# SPTSquidBoard.net
KiCad netlist of a schematic drawn in Altium Designer
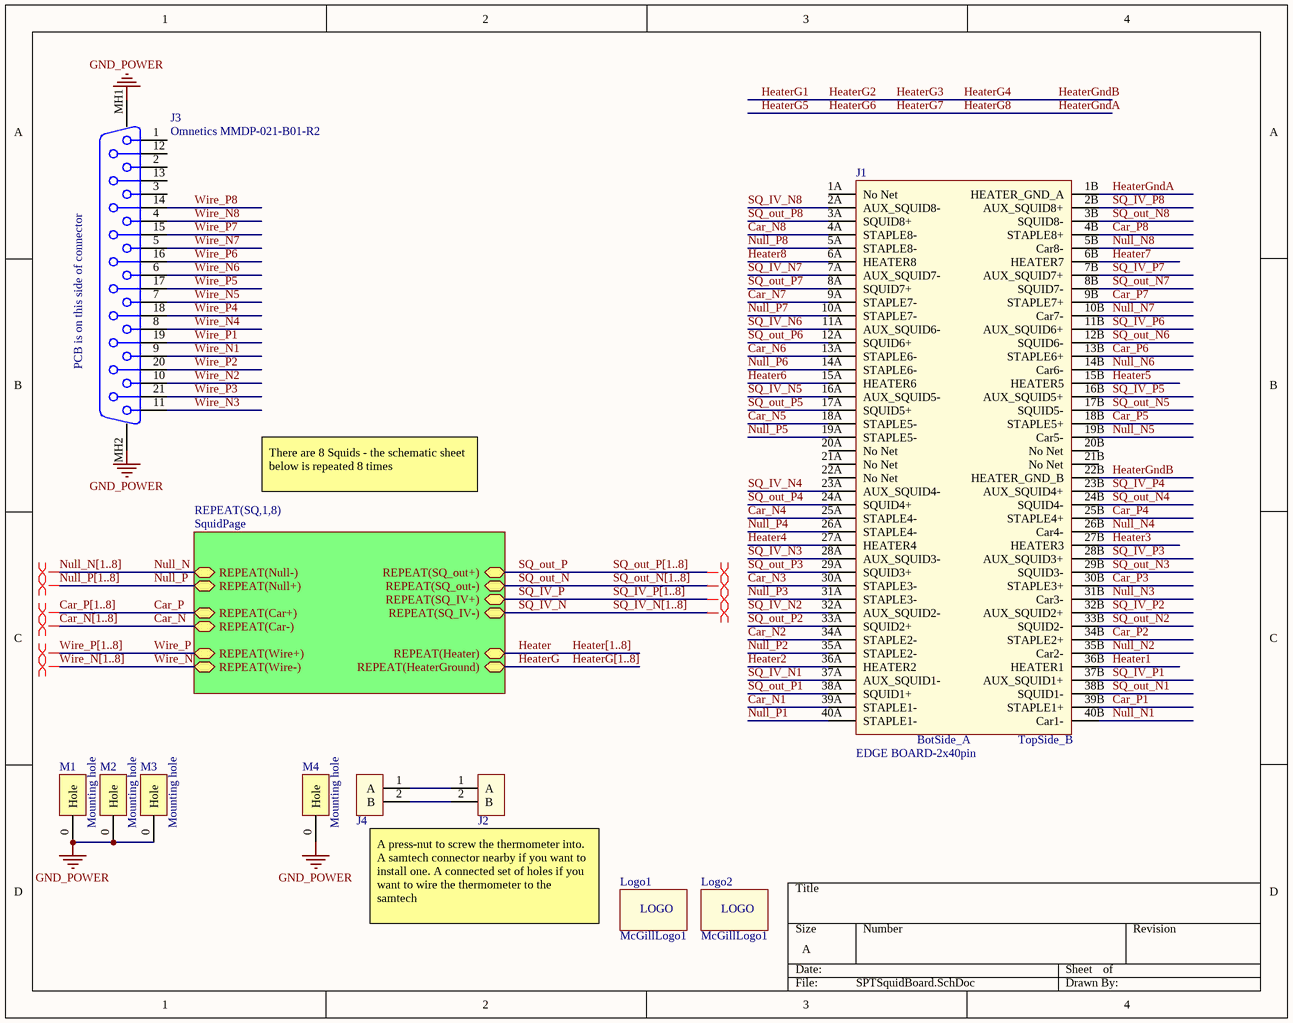
[diagram p0: SPTSquidBoard.SchDoc]

(export (version "E")
  (design (tool "Eeschema 10.0.6"))
  (components
    (comp (ref "J1")
      (value "EDGE BOARD-2x40pin")
      (description "Edge connector")
      (libsource (lib "SPT3G_LCBoard") (part "EDGE BOARD-2x40pin"))
    )
    (comp (ref "J2")
      (value "TempSenseWireConnection")
      (footprint "TempSenseWireCons")
      (libsource (lib "SPT3G_LCBoard") (part "TempSenseCon"))
    )
    (comp (ref "J3")
      (value "Omnetics MMDP-021-B01-R2")
      (footprint "MMDP-021-B02-R2")
      (description "OmneticsMicroD21")
      (libsource (lib "SPT3G_LCBoard") (part "OmneticsMicroD21"))
    )
    (comp (ref "J4")
      (value "TempSenseWireConnection")
      (footprint "TempSenseWireCons")
      (libsource (lib "") (part "TempSenseCon_1"))
    )
    (comp (ref "Logo1")
      (value "McGillLogo1")
      (footprint "McGillLogo1")
      (libsource (lib "SPT3G_LCBoard") (part "Logo"))
    )
    (comp (ref "Logo2")
      (value "McGillLogo1")
      (footprint "McGillLogo1")
      (libsource (lib "SPT3G_LCBoard") (part "Logo"))
    )
    (comp (ref "M1")
      (value "Mounting hole")
      (footprint "MountingHoleSquidBoard")
      (libsource (lib "SPT3G_LCBoard") (part "SquidBoardMountingHole"))
    )
    (comp (ref "M2")
      (value "Mounting hole")
      (footprint "MountingHoleSquidBoard")
      (libsource (lib "SPT3G_LCBoard") (part "SquidBoardMountingHole"))
    )
    (comp (ref "M3")
      (value "Mounting hole")
      (footprint "MountingHoleSquidBoard")
      (libsource (lib "SPT3G_LCBoard") (part "SquidBoardMountingHole"))
    )
    (comp (ref "M4")
      (value "Mounting hole")
      (footprint "MountingHoleSquidBoard")
      (libsource (lib "SPT3G_LCBoard") (part "SquidBoardMountingHole"))
    )
  )
  (nets
    (net (code "2") (name "/Car_N1") (class "Default")
      (node (ref "J1") (pin "39A") (pinfunction "STAPLE1-_39A") (pintype "passive"))
    )
    (net (code "3") (name "/Car_N2") (class "Default")
      (node (ref "J1") (pin "34A") (pinfunction "STAPLE2-_34A") (pintype "passive"))
    )
    (net (code "4") (name "/Car_N3") (class "Default")
      (node (ref "J1") (pin "30A") (pinfunction "STAPLE3-_30A") (pintype "passive"))
    )
    (net (code "5") (name "/Car_N4") (class "Default")
      (node (ref "J1") (pin "25A") (pinfunction "STAPLE4-_25A") (pintype "passive"))
    )
    (net (code "6") (name "/Car_N5") (class "Default")
      (node (ref "J1") (pin "18A") (pinfunction "STAPLE5-_18A") (pintype "passive"))
    )
    (net (code "7") (name "/Car_N6") (class "Default")
      (node (ref "J1") (pin "13A") (pinfunction "STAPLE6-_13A") (pintype "passive"))
    )
    (net (code "8") (name "/Car_N7") (class "Default")
      (node (ref "J1") (pin "9A") (pinfunction "STAPLE7-_9A") (pintype "passive"))
    )
    (net (code "9") (name "/Car_N8") (class "Default")
      (node (ref "J1") (pin "4A") (pinfunction "STAPLE8-_4A") (pintype "passive"))
    )
    (net (code "12") (name "/Car_P1") (class "Default")
      (node (ref "J1") (pin "39B") (pinfunction "STAPLE1+_39B") (pintype "passive"))
    )
    (net (code "13") (name "/Car_P2") (class "Default")
      (node (ref "J1") (pin "34B") (pinfunction "STAPLE2+_34B") (pintype "passive"))
    )
    (net (code "14") (name "/Car_P3") (class "Default")
      (node (ref "J1") (pin "30B") (pinfunction "STAPLE3+_30B") (pintype "passive"))
    )
    (net (code "15") (name "/Car_P4") (class "Default")
      (node (ref "J1") (pin "25B") (pinfunction "STAPLE4+_25B") (pintype "passive"))
    )
    (net (code "16") (name "/Car_P5") (class "Default")
      (node (ref "J1") (pin "18B") (pinfunction "STAPLE5+_18B") (pintype "passive"))
    )
    (net (code "17") (name "/Car_P6") (class "Default")
      (node (ref "J1") (pin "13B") (pinfunction "STAPLE6+_13B") (pintype "passive"))
    )
    (net (code "18") (name "/Car_P7") (class "Default")
      (node (ref "J1") (pin "9B") (pinfunction "STAPLE7+_9B") (pintype "passive"))
    )
    (net (code "19") (name "/Car_P8") (class "Default")
      (node (ref "J1") (pin "4B") (pinfunction "STAPLE8+_4B") (pintype "passive"))
    )
    (net (code "22") (name "/Heater1") (class "Default")
      (node (ref "J1") (pin "36B") (pinfunction "HEATER1_36B") (pintype "passive"))
    )
    (net (code "23") (name "/Heater2") (class "Default")
      (node (ref "J1") (pin "36A") (pinfunction "HEATER2_36A") (pintype "passive"))
    )
    (net (code "24") (name "/Heater3") (class "Default")
      (node (ref "J1") (pin "27B") (pinfunction "HEATER3_27B") (pintype "passive"))
    )
    (net (code "25") (name "/Heater4") (class "Default")
      (node (ref "J1") (pin "27A") (pinfunction "HEATER4_27A") (pintype "passive"))
    )
    (net (code "26") (name "/Heater5") (class "Default")
      (node (ref "J1") (pin "15B") (pinfunction "HEATER5_15B") (pintype "passive"))
    )
    (net (code "27") (name "/Heater6") (class "Default")
      (node (ref "J1") (pin "15A") (pinfunction "HEATER6_15A") (pintype "passive"))
    )
    (net (code "28") (name "/Heater7") (class "Default")
      (node (ref "J1") (pin "6B") (pinfunction "HEATER7_6B") (pintype "passive"))
    )
    (net (code "29") (name "/Heater8") (class "Default")
      (node (ref "J1") (pin "6A") (pinfunction "HEATER8_6A") (pintype "passive"))
    )
    (net (code "31") (name "/HeaterG1") (class "Default")
      (node (ref "J1") (pin "22B") (pinfunction "HEATER_GND_B_22B") (pintype "passive"))
    )
    (net (code "32") (name "/HeaterG5") (class "Default")
      (node (ref "J1") (pin "1B") (pinfunction "HEATER_GND_A_1B") (pintype "passive"))
    )
    (net (code "34") (name "/Null_N1") (class "Default")
      (node (ref "J1") (pin "40B") (pinfunction "Car1-_40B") (pintype "passive"))
    )
    (net (code "35") (name "/Null_N2") (class "Default")
      (node (ref "J1") (pin "35B") (pinfunction "Car2-_35B") (pintype "passive"))
    )
    (net (code "36") (name "/Null_N3") (class "Default")
      (node (ref "J1") (pin "31B") (pinfunction "Car3-_31B") (pintype "passive"))
    )
    (net (code "37") (name "/Null_N4") (class "Default")
      (node (ref "J1") (pin "26B") (pinfunction "Car4-_26B") (pintype "passive"))
    )
    (net (code "38") (name "/Null_N5") (class "Default")
      (node (ref "J1") (pin "19B") (pinfunction "Car5-_19B") (pintype "passive"))
    )
    (net (code "39") (name "/Null_N6") (class "Default")
      (node (ref "J1") (pin "14B") (pinfunction "Car6-_14B") (pintype "passive"))
    )
    (net (code "40") (name "/Null_N7") (class "Default")
      (node (ref "J1") (pin "10B") (pinfunction "Car7-_10B") (pintype "passive"))
    )
    (net (code "41") (name "/Null_N8") (class "Default")
      (node (ref "J1") (pin "5B") (pinfunction "Car8-_5B") (pintype "passive"))
    )
    (net (code "44") (name "/Null_P1") (class "Default")
      (node (ref "J1") (pin "40A") (pinfunction "STAPLE1-_40A") (pintype "passive"))
    )
    (net (code "45") (name "/Null_P2") (class "Default")
      (node (ref "J1") (pin "35A") (pinfunction "STAPLE2-_35A") (pintype "passive"))
    )
    (net (code "46") (name "/Null_P3") (class "Default")
      (node (ref "J1") (pin "31A") (pinfunction "STAPLE3-_31A") (pintype "passive"))
    )
    (net (code "47") (name "/Null_P4") (class "Default")
      (node (ref "J1") (pin "26A") (pinfunction "STAPLE4-_26A") (pintype "passive"))
    )
    (net (code "48") (name "/Null_P5") (class "Default")
      (node (ref "J1") (pin "19A") (pinfunction "STAPLE5-_19A") (pintype "passive"))
    )
    (net (code "49") (name "/Null_P6") (class "Default")
      (node (ref "J1") (pin "14A") (pinfunction "STAPLE6-_14A") (pintype "passive"))
    )
    (net (code "50") (name "/Null_P7") (class "Default")
      (node (ref "J1") (pin "10A") (pinfunction "STAPLE7-_10A") (pintype "passive"))
    )
    (net (code "51") (name "/Null_P8") (class "Default")
      (node (ref "J1") (pin "5A") (pinfunction "STAPLE8-_5A") (pintype "passive"))
    )
    (net (code "54") (name "/SQ_IV_N1") (class "Default")
      (node (ref "J1") (pin "37A") (pinfunction "AUX_SQUID1-_37A") (pintype "passive"))
    )
    (net (code "55") (name "/SQ_IV_N2") (class "Default")
      (node (ref "J1") (pin "32A") (pinfunction "AUX_SQUID2-_32A") (pintype "passive"))
    )
    (net (code "56") (name "/SQ_IV_N3") (class "Default")
      (node (ref "J1") (pin "28A") (pinfunction "AUX_SQUID3-_28A") (pintype "passive"))
    )
    (net (code "57") (name "/SQ_IV_N4") (class "Default")
      (node (ref "J1") (pin "23A") (pinfunction "AUX_SQUID4-_23A") (pintype "passive"))
    )
    (net (code "58") (name "/SQ_IV_N5") (class "Default")
      (node (ref "J1") (pin "16A") (pinfunction "AUX_SQUID5-_16A") (pintype "passive"))
    )
    (net (code "59") (name "/SQ_IV_N6") (class "Default")
      (node (ref "J1") (pin "11A") (pinfunction "AUX_SQUID6-_11A") (pintype "passive"))
    )
    (net (code "60") (name "/SQ_IV_N7") (class "Default")
      (node (ref "J1") (pin "7A") (pinfunction "AUX_SQUID7-_7A") (pintype "passive"))
    )
    (net (code "61") (name "/SQ_IV_N8") (class "Default")
      (node (ref "J1") (pin "2A") (pinfunction "AUX_SQUID8-_2A") (pintype "passive"))
    )
    (net (code "64") (name "/SQ_IV_P1") (class "Default")
      (node (ref "J1") (pin "37B") (pinfunction "AUX_SQUID1+_37B") (pintype "passive"))
    )
    (net (code "65") (name "/SQ_IV_P2") (class "Default")
      (node (ref "J1") (pin "32B") (pinfunction "AUX_SQUID2+_32B") (pintype "passive"))
    )
    (net (code "66") (name "/SQ_IV_P3") (class "Default")
      (node (ref "J1") (pin "28B") (pinfunction "AUX_SQUID3+_28B") (pintype "passive"))
    )
    (net (code "67") (name "/SQ_IV_P4") (class "Default")
      (node (ref "J1") (pin "23B") (pinfunction "AUX_SQUID4+_23B") (pintype "passive"))
    )
    (net (code "68") (name "/SQ_IV_P5") (class "Default")
      (node (ref "J1") (pin "16B") (pinfunction "AUX_SQUID5+_16B") (pintype "passive"))
    )
    (net (code "69") (name "/SQ_IV_P6") (class "Default")
      (node (ref "J1") (pin "11B") (pinfunction "AUX_SQUID6+_11B") (pintype "passive"))
    )
    (net (code "70") (name "/SQ_IV_P7") (class "Default")
      (node (ref "J1") (pin "7B") (pinfunction "AUX_SQUID7+_7B") (pintype "passive"))
    )
    (net (code "71") (name "/SQ_IV_P8") (class "Default")
      (node (ref "J1") (pin "2B") (pinfunction "AUX_SQUID8+_2B") (pintype "passive"))
    )
    (net (code "74") (name "/SQ_out_N1") (class "Default")
      (node (ref "J1") (pin "38B") (pinfunction "SQUID1-_38B") (pintype "passive"))
    )
    (net (code "75") (name "/SQ_out_N2") (class "Default")
      (node (ref "J1") (pin "33B") (pinfunction "SQUID2-_33B") (pintype "passive"))
    )
    (net (code "76") (name "/SQ_out_N3") (class "Default")
      (node (ref "J1") (pin "29B") (pinfunction "SQUID3-_29B") (pintype "passive"))
    )
    (net (code "77") (name "/SQ_out_N4") (class "Default")
      (node (ref "J1") (pin "24B") (pinfunction "SQUID4-_24B") (pintype "passive"))
    )
    (net (code "78") (name "/SQ_out_N5") (class "Default")
      (node (ref "J1") (pin "17B") (pinfunction "SQUID5-_17B") (pintype "passive"))
    )
    (net (code "79") (name "/SQ_out_N6") (class "Default")
      (node (ref "J1") (pin "12B") (pinfunction "SQUID6-_12B") (pintype "passive"))
    )
    (net (code "80") (name "/SQ_out_N7") (class "Default")
      (node (ref "J1") (pin "8B") (pinfunction "SQUID7-_8B") (pintype "passive"))
    )
    (net (code "81") (name "/SQ_out_N8") (class "Default")
      (node (ref "J1") (pin "3B") (pinfunction "SQUID8-_3B") (pintype "passive"))
    )
    (net (code "84") (name "/SQ_out_P1") (class "Default")
      (node (ref "J1") (pin "38A") (pinfunction "SQUID1+_38A") (pintype "passive"))
    )
    (net (code "85") (name "/SQ_out_P2") (class "Default")
      (node (ref "J1") (pin "33A") (pinfunction "SQUID2+_33A") (pintype "passive"))
    )
    (net (code "86") (name "/SQ_out_P3") (class "Default")
      (node (ref "J1") (pin "29A") (pinfunction "SQUID3+_29A") (pintype "passive"))
    )
    (net (code "87") (name "/SQ_out_P4") (class "Default")
      (node (ref "J1") (pin "24A") (pinfunction "SQUID4+_24A") (pintype "passive"))
    )
    (net (code "88") (name "/SQ_out_P5") (class "Default")
      (node (ref "J1") (pin "17A") (pinfunction "SQUID5+_17A") (pintype "passive"))
    )
    (net (code "89") (name "/SQ_out_P6") (class "Default")
      (node (ref "J1") (pin "12A") (pinfunction "SQUID6+_12A") (pintype "passive"))
    )
    (net (code "90") (name "/SQ_out_P7") (class "Default")
      (node (ref "J1") (pin "8A") (pinfunction "SQUID7+_8A") (pintype "passive"))
    )
    (net (code "91") (name "/SQ_out_P8") (class "Default")
      (node (ref "J1") (pin "3A") (pinfunction "SQUID8+_3A") (pintype "passive"))
    )
    (net (code "94") (name "/Wire_N1") (class "Default")
      (node (ref "J3") (pin "9") (pinfunction "9_9") (pintype "passive"))
    )
    (net (code "95") (name "/Wire_N2") (class "Default")
      (node (ref "J3") (pin "10") (pinfunction "10_10") (pintype "passive"))
    )
    (net (code "96") (name "/Wire_N3") (class "Default")
      (node (ref "J3") (pin "11") (pinfunction "11_11") (pintype "passive"))
    )
    (net (code "97") (name "/Wire_N4") (class "Default")
      (node (ref "J3") (pin "8") (pinfunction "8_8") (pintype "passive"))
    )
    (net (code "98") (name "/Wire_N5") (class "Default")
      (node (ref "J3") (pin "7") (pinfunction "7_7") (pintype "passive"))
    )
    (net (code "99") (name "/Wire_N6") (class "Default")
      (node (ref "J3") (pin "6") (pinfunction "6_6") (pintype "passive"))
    )
    (net (code "100") (name "/Wire_N7") (class "Default")
      (node (ref "J3") (pin "5") (pinfunction "5_5") (pintype "passive"))
    )
    (net (code "101") (name "/Wire_N8") (class "Default")
      (node (ref "J3") (pin "4") (pinfunction "4_4") (pintype "passive"))
    )
    (net (code "104") (name "/Wire_P1") (class "Default")
      (node (ref "J3") (pin "19") (pinfunction "19_19") (pintype "passive"))
    )
    (net (code "105") (name "/Wire_P2") (class "Default")
      (node (ref "J3") (pin "20") (pinfunction "20_20") (pintype "passive"))
    )
    (net (code "106") (name "/Wire_P3") (class "Default")
      (node (ref "J3") (pin "21") (pinfunction "21_21") (pintype "passive"))
    )
    (net (code "107") (name "/Wire_P4") (class "Default")
      (node (ref "J3") (pin "18") (pinfunction "18_18") (pintype "passive"))
    )
    (net (code "108") (name "/Wire_P5") (class "Default")
      (node (ref "J3") (pin "17") (pinfunction "17_17") (pintype "passive"))
    )
    (net (code "109") (name "/Wire_P6") (class "Default")
      (node (ref "J3") (pin "16") (pinfunction "16_16") (pintype "passive"))
    )
    (net (code "110") (name "/Wire_P7") (class "Default")
      (node (ref "J3") (pin "15") (pinfunction "15_15") (pintype "passive"))
    )
    (net (code "111") (name "/Wire_P8") (class "Default")
      (node (ref "J3") (pin "14") (pinfunction "14_14") (pintype "passive"))
    )
    (net (code "113") (name "GND_POWER") (class "Default")
      (node (ref "J3") (pin "MH1") (pinfunction "MH1_MH1") (pintype "passive"))
      (node (ref "J3") (pin "MH2") (pinfunction "MH2_MH2") (pintype "passive"))
      (node (ref "M1") (pin "0") (pinfunction "Hole_0") (pintype "passive"))
      (node (ref "M2") (pin "0") (pinfunction "Hole_0") (pintype "passive"))
      (node (ref "M3") (pin "0") (pinfunction "Hole_0") (pintype "passive"))
      (node (ref "M4") (pin "0") (pinfunction "Hole_0") (pintype "passive"))
    )
    (net (code "114") (name "Net-(J2-A)") (class "Default")
      (node (ref "J2") (pin "1") (pinfunction "A_1") (pintype "passive"))
      (node (ref "J4") (pin "1") (pinfunction "A_1") (pintype "passive"))
    )
    (net (code "115") (name "Net-(J2-B)") (class "Default")
      (node (ref "J2") (pin "2") (pinfunction "B_2") (pintype "passive"))
      (node (ref "J4") (pin "2") (pinfunction "B_2") (pintype "passive"))
    )
    (net (code "116") (name "unconnected-(J1-No_Net-Pad1A)") (class "Default")
      (node (ref "J1") (pin "1A") (pinfunction "No_Net_1A") (pintype "passive"))
    )
    (net (code "117") (name "unconnected-(J1-No_Net-Pad20A)") (class "Default")
      (node (ref "J1") (pin "20A") (pinfunction "No_Net_20A") (pintype "passive"))
    )
    (net (code "118") (name "unconnected-(J1-No_Net-Pad20B)") (class "Default")
      (node (ref "J1") (pin "20B") (pinfunction "No_Net_20B") (pintype "passive"))
    )
    (net (code "119") (name "unconnected-(J1-No_Net-Pad21A)") (class "Default")
      (node (ref "J1") (pin "21A") (pinfunction "No_Net_21A") (pintype "passive"))
    )
    (net (code "120") (name "unconnected-(J1-No_Net-Pad21B)") (class "Default")
      (node (ref "J1") (pin "21B") (pinfunction "No_Net_21B") (pintype "passive"))
    )
    (net (code "121") (name "unconnected-(J1-No_Net-Pad22A)") (class "Default")
      (node (ref "J1") (pin "22A") (pinfunction "No_Net_22A") (pintype "passive"))
    )
    (net (code "122") (name "unconnected-(J3-Pad1)") (class "Default")
      (node (ref "J3") (pin "1") (pinfunction "1_1") (pintype "passive"))
    )
    (net (code "123") (name "unconnected-(J3-Pad2)") (class "Default")
      (node (ref "J3") (pin "2") (pinfunction "2_2") (pintype "passive"))
    )
    (net (code "124") (name "unconnected-(J3-Pad3)") (class "Default")
      (node (ref "J3") (pin "3") (pinfunction "3_3") (pintype "passive"))
    )
    (net (code "125") (name "unconnected-(J3-Pad12)") (class "Default")
      (node (ref "J3") (pin "12") (pinfunction "12_12") (pintype "passive"))
    )
    (net (code "126") (name "unconnected-(J3-Pad13)") (class "Default")
      (node (ref "J3") (pin "13") (pinfunction "13_13") (pintype "passive"))
    )
  )
)
